# CPU.net
KiCad netlist of a schematic drawn in Altium Designer
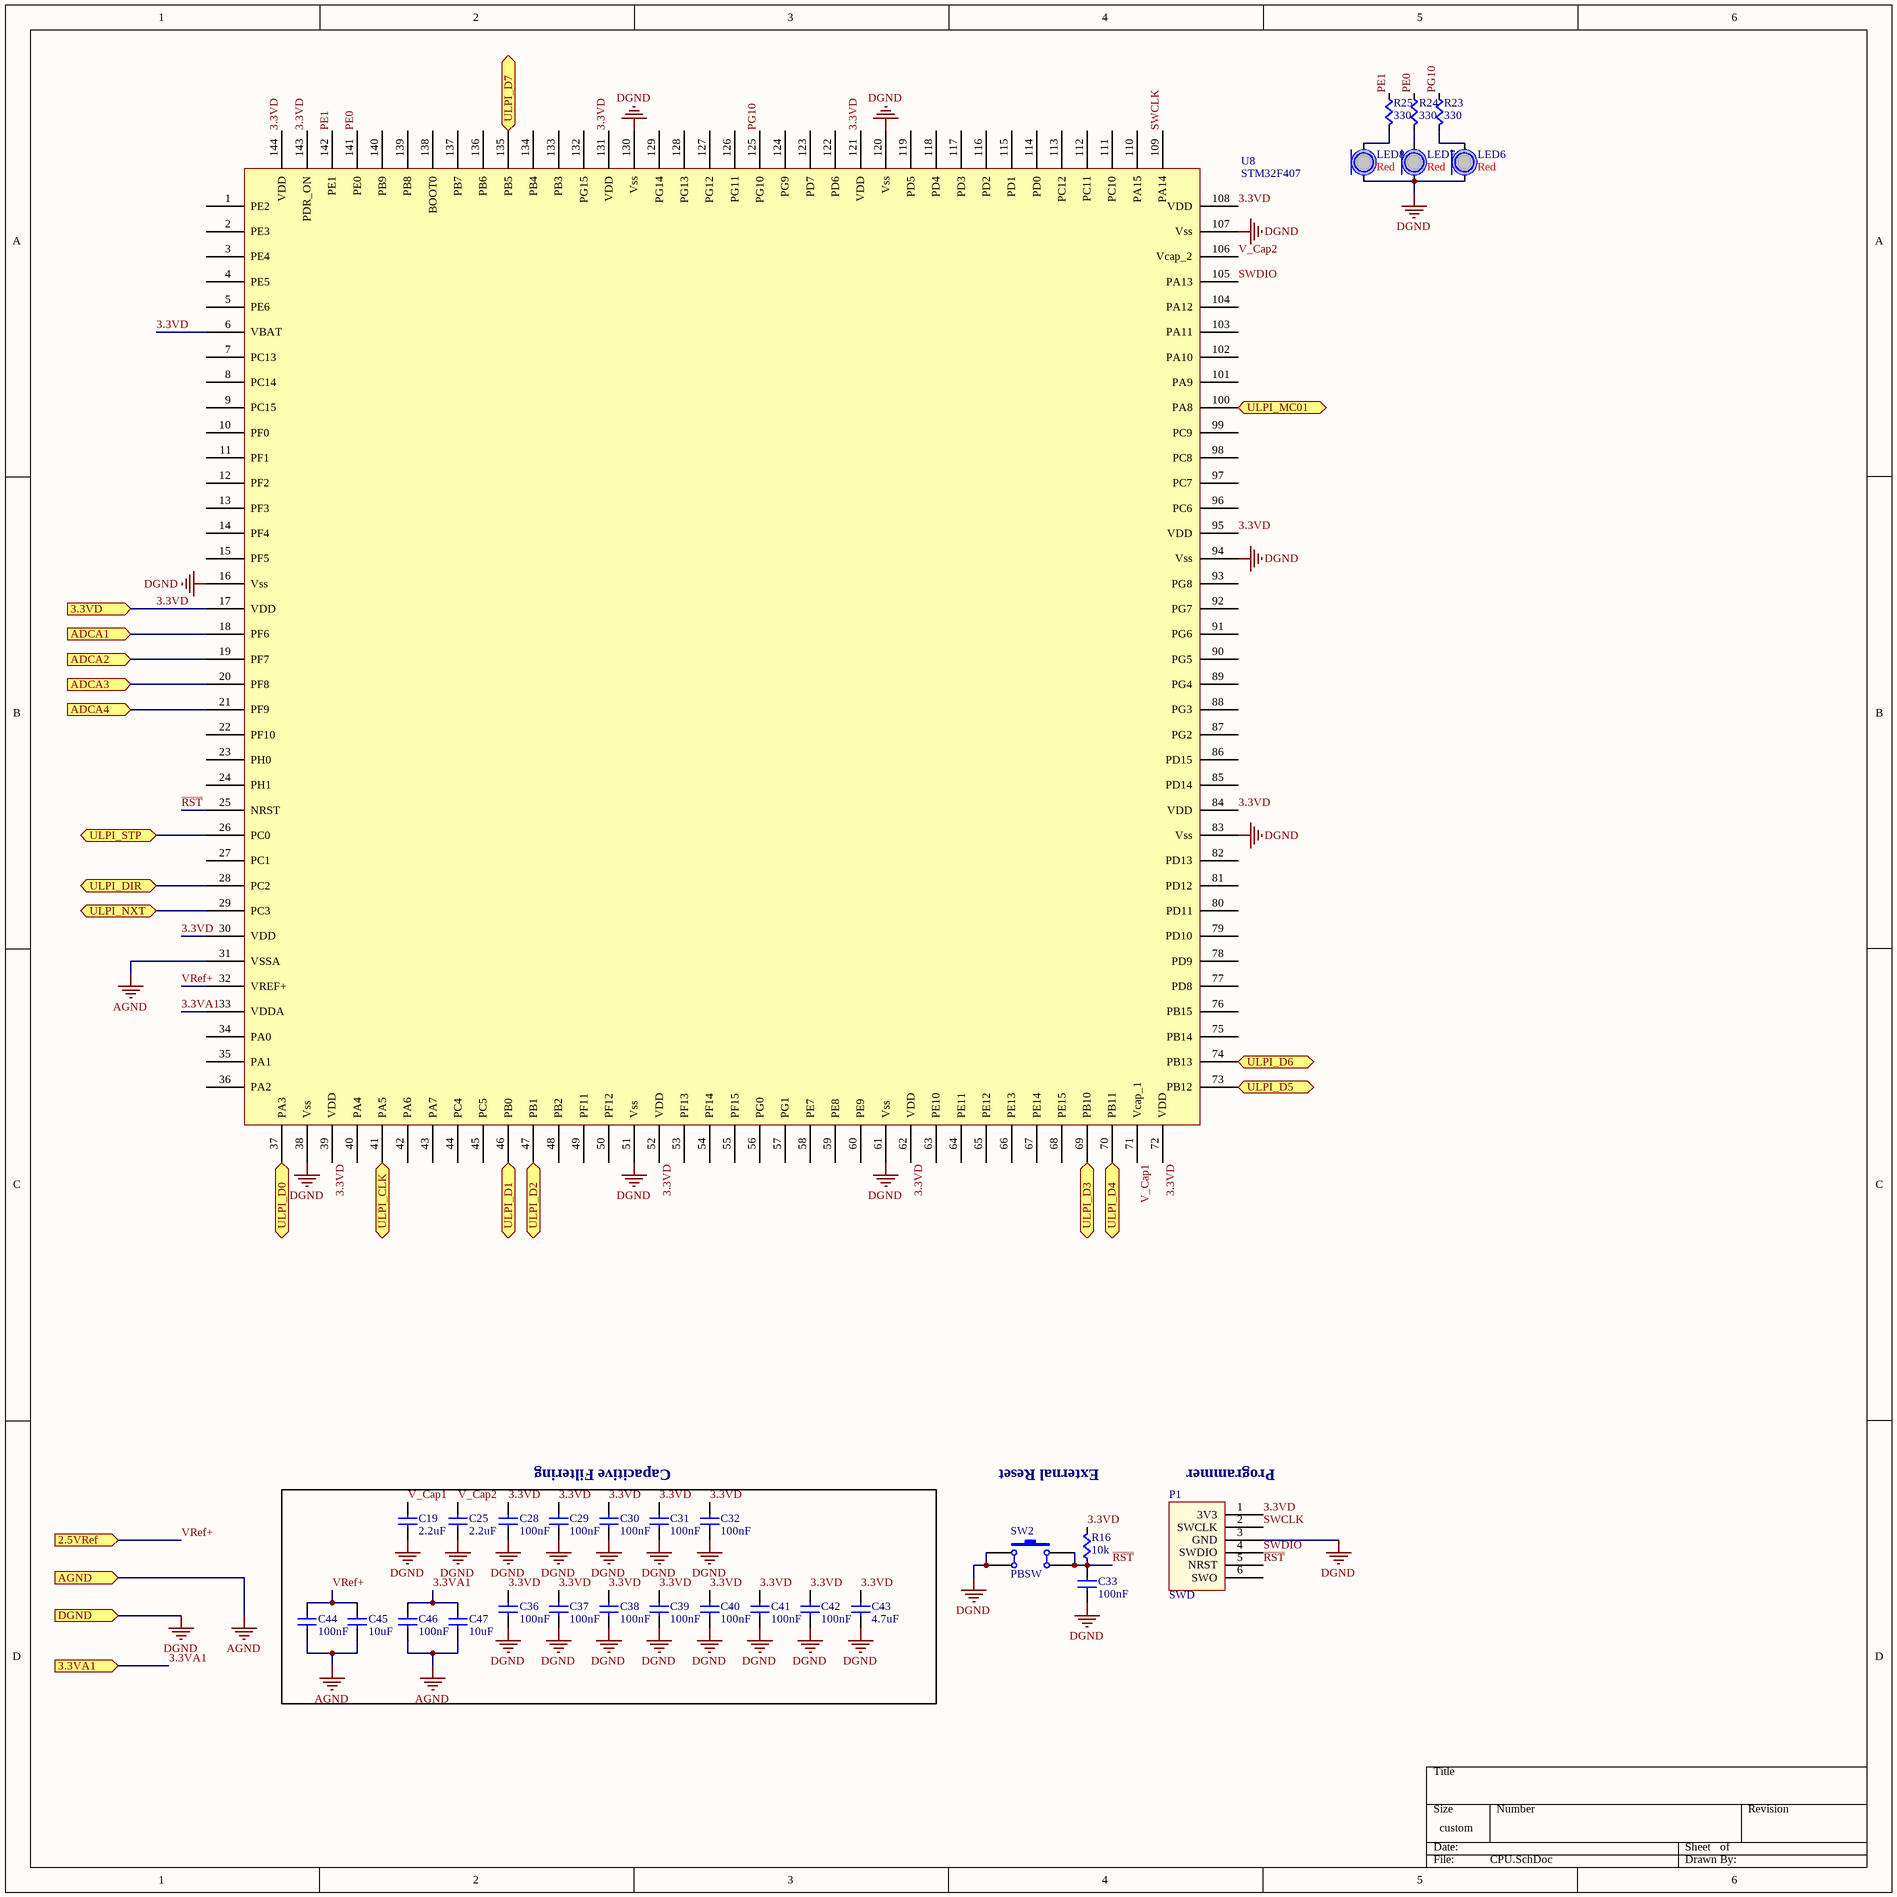
[diagram p0: CPU.SchDoc]

(export (version "E")
  (design (tool "Eeschema 10.0.6"))
  (components
    (comp (ref "C19")
      (value "2.2uF")
      (footprint "CAPC0603")
      (fields (field (name "Comment") "Cap"))
      (libsource (lib "SubjuGator8") (part "Cap"))
    )
    (comp (ref "C25")
      (value "2.2uF")
      (footprint "CAPC0603")
      (fields (field (name "Comment") "Cap"))
      (libsource (lib "SubjuGator8") (part "Cap"))
    )
    (comp (ref "C28")
      (value "100nF")
      (footprint "CAPC0603")
      (fields (field (name "Comment") "Cap"))
      (libsource (lib "SubjuGator8") (part "Cap"))
    )
    (comp (ref "C29")
      (value "100nF")
      (footprint "CAPC0603")
      (fields (field (name "Comment") "Cap"))
      (libsource (lib "SubjuGator8") (part "Cap"))
    )
    (comp (ref "C30")
      (value "100nF")
      (footprint "CAPC0603")
      (fields (field (name "Comment") "Cap"))
      (libsource (lib "SubjuGator8") (part "Cap"))
    )
    (comp (ref "C31")
      (value "100nF")
      (footprint "CAPC0603")
      (fields (field (name "Comment") "Cap"))
      (libsource (lib "SubjuGator8") (part "Cap"))
    )
    (comp (ref "C32")
      (value "100nF")
      (footprint "CAPC0603")
      (fields (field (name "Comment") "Cap"))
      (libsource (lib "SubjuGator8") (part "Cap"))
    )
    (comp (ref "C33")
      (value "100nF")
      (footprint "CAPC0603")
      (fields (field (name "Comment") "Cap"))
      (libsource (lib "SubjuGator8") (part "Cap"))
    )
    (comp (ref "C36")
      (value "100nF")
      (footprint "CAPC0603")
      (fields (field (name "Comment") "Cap"))
      (libsource (lib "SubjuGator8") (part "Cap"))
    )
    (comp (ref "C37")
      (value "100nF")
      (footprint "CAPC0603")
      (fields (field (name "Comment") "Cap"))
      (libsource (lib "SubjuGator8") (part "Cap"))
    )
    (comp (ref "C38")
      (value "100nF")
      (footprint "CAPC0603")
      (fields (field (name "Comment") "Cap"))
      (libsource (lib "SubjuGator8") (part "Cap"))
    )
    (comp (ref "C39")
      (value "100nF")
      (footprint "CAPC0603")
      (fields (field (name "Comment") "Cap"))
      (libsource (lib "SubjuGator8") (part "Cap"))
    )
    (comp (ref "C40")
      (value "100nF")
      (footprint "CAPC0603")
      (fields (field (name "Comment") "Cap"))
      (libsource (lib "SubjuGator8") (part "Cap"))
    )
    (comp (ref "C41")
      (value "100nF")
      (footprint "CAPC0603")
      (fields (field (name "Comment") "Cap"))
      (libsource (lib "SubjuGator8") (part "Cap"))
    )
    (comp (ref "C42")
      (value "100nF")
      (footprint "CAPC0603")
      (fields (field (name "Comment") "Cap"))
      (libsource (lib "SubjuGator8") (part "Cap"))
    )
    (comp (ref "C43")
      (value "4.7uF")
      (footprint "CAPC0603")
      (fields (field (name "Comment") "Cap"))
      (libsource (lib "SubjuGator8") (part "Cap"))
    )
    (comp (ref "C44")
      (value "100nF")
      (footprint "CAPC0603")
      (fields (field (name "Comment") "Cap"))
      (libsource (lib "SubjuGator8") (part "Cap"))
    )
    (comp (ref "C45")
      (value "10uF")
      (footprint "CAPC0603")
      (fields (field (name "Comment") "Cap"))
      (libsource (lib "SubjuGator8") (part "Cap"))
    )
    (comp (ref "C46")
      (value "100nF")
      (footprint "CAPC0603")
      (fields (field (name "Comment") "Cap"))
      (libsource (lib "SubjuGator8") (part "Cap"))
    )
    (comp (ref "C47")
      (value "10uF")
      (footprint "CAPC0603")
      (fields (field (name "Comment") "Cap"))
      (libsource (lib "SubjuGator8") (part "Cap"))
    )
    (comp (ref "LED6")
      (value "LED")
      (footprint "LED0603")
      (fields (field (name "COLOR") "Red"))
      (libsource (lib "Semiconductors") (part "LED"))
    )
    (comp (ref "LED7")
      (value "LED")
      (footprint "LED0603")
      (fields (field (name "COLOR") "Red"))
      (libsource (lib "Semiconductors") (part "LED"))
    )
    (comp (ref "LED8")
      (value "LED")
      (footprint "LED0603")
      (fields (field (name "COLOR") "Red"))
      (libsource (lib "Semiconductors") (part "LED"))
    )
    (comp (ref "P1")
      (value "SWD")
      (footprint "SWD_STM32")
      (description "SWD connector matching the pinout on STM Discovery Boards")
      (libsource (lib "SubjuGator8") (part "SWD_STM32"))
    )
    (comp (ref "R16")
      (value "10k")
      (footprint "RES0603")
      (fields (field (name "Comment") "Res"))
      (libsource (lib "Passives") (part "Res"))
    )
    (comp (ref "R23")
      (value "330")
      (footprint "RES0603")
      (fields (field (name "Comment") "Res"))
      (libsource (lib "Passives") (part "Res"))
    )
    (comp (ref "R24")
      (value "330")
      (footprint "RES0603")
      (fields (field (name "Comment") "Res"))
      (libsource (lib "Passives") (part "Res"))
    )
    (comp (ref "R25")
      (value "330")
      (footprint "RES0603")
      (fields (field (name "Comment") "Res"))
      (libsource (lib "Passives") (part "Res"))
    )
    (comp (ref "SW2")
      (value "PBSW")
      (footprint "Hydrophone:PBSW")
      (description "Push Button Switch")
      (fields
        (field (name "MANUFACTURER") "Panasonic Electronic Components")
        (field (name "MANUFACTURER PART NUMBER") "EVQ-9P105M")
        (field (name "PUBLISHER") "Altium Limited")
      )
      (libsource (lib "Hydrophone") (part "SW-PB"))
    )
    (comp (ref "U8")
      (value "STM32F407")
      (footprint "LQFP-144")
      (description "IC MCU 32BIT 1MB FLASH 144LQFP")
      (libsource (lib "SubjuGator8") (part "STM32F407ZGT6"))
    )
  )
  (nets
    (net (code "1") (name "/3.3VA1") (class "Default")
      (node (ref "C46") (pin "1") (pinfunction "A_1") (pintype "passive"))
      (node (ref "C47") (pin "1") (pinfunction "A_1") (pintype "passive"))
      (node (ref "U8") (pin "33") (pinfunction "VDDA_33") (pintype "passive"))
    )
    (net (code "2") (name "/3.3VD") (class "Default")
      (node (ref "C28") (pin "1") (pinfunction "A_1") (pintype "passive"))
      (node (ref "C29") (pin "1") (pinfunction "A_1") (pintype "passive"))
      (node (ref "C30") (pin "1") (pinfunction "A_1") (pintype "passive"))
      (node (ref "C31") (pin "1") (pinfunction "A_1") (pintype "passive"))
      (node (ref "C32") (pin "1") (pinfunction "A_1") (pintype "passive"))
      (node (ref "C36") (pin "1") (pinfunction "A_1") (pintype "passive"))
      (node (ref "C37") (pin "1") (pinfunction "A_1") (pintype "passive"))
      (node (ref "C38") (pin "1") (pinfunction "A_1") (pintype "passive"))
      (node (ref "C39") (pin "1") (pinfunction "A_1") (pintype "passive"))
      (node (ref "C40") (pin "1") (pinfunction "A_1") (pintype "passive"))
      (node (ref "C41") (pin "1") (pinfunction "A_1") (pintype "passive"))
      (node (ref "C42") (pin "1") (pinfunction "A_1") (pintype "passive"))
      (node (ref "C43") (pin "1") (pinfunction "A_1") (pintype "passive"))
      (node (ref "P1") (pin "1") (pinfunction "3V3_1") (pintype "passive"))
      (node (ref "R16") (pin "1") (pinfunction "A_1") (pintype "passive"))
      (node (ref "U8") (pin "108") (pinfunction "VDD_108") (pintype "passive"))
      (node (ref "U8") (pin "121") (pinfunction "VDD_121") (pintype "passive"))
      (node (ref "U8") (pin "131") (pinfunction "VDD_131") (pintype "passive"))
      (node (ref "U8") (pin "143") (pinfunction "PDR_ON_143") (pintype "passive"))
      (node (ref "U8") (pin "144") (pinfunction "VDD_144") (pintype "passive"))
      (node (ref "U8") (pin "17") (pinfunction "VDD_17") (pintype "passive"))
      (node (ref "U8") (pin "30") (pinfunction "VDD_30") (pintype "passive"))
      (node (ref "U8") (pin "39") (pinfunction "VDD_39") (pintype "passive"))
      (node (ref "U8") (pin "52") (pinfunction "VDD_52") (pintype "passive"))
      (node (ref "U8") (pin "6") (pinfunction "VBAT_6") (pintype "passive"))
      (node (ref "U8") (pin "62") (pinfunction "VDD_62") (pintype "passive"))
      (node (ref "U8") (pin "72") (pinfunction "VDD_72") (pintype "passive"))
      (node (ref "U8") (pin "84") (pinfunction "VDD_84") (pintype "passive"))
      (node (ref "U8") (pin "95") (pinfunction "VDD_95") (pintype "passive"))
    )
    (net (code "3") (name "/ADCA1") (class "Default")
      (node (ref "U8") (pin "18") (pinfunction "PF6_18") (pintype "passive"))
    )
    (net (code "4") (name "/ADCA2") (class "Default")
      (node (ref "U8") (pin "19") (pinfunction "PF7_19") (pintype "passive"))
    )
    (net (code "5") (name "/ADCA3") (class "Default")
      (node (ref "U8") (pin "20") (pinfunction "PF8_20") (pintype "passive"))
    )
    (net (code "6") (name "/ADCA4") (class "Default")
      (node (ref "U8") (pin "21") (pinfunction "PF9_21") (pintype "passive"))
    )
    (net (code "7") (name "/PE0") (class "Default")
      (node (ref "R24") (pin "2") (pinfunction "B_2") (pintype "passive"))
      (node (ref "U8") (pin "141") (pinfunction "PE0_141") (pintype "passive"))
    )
    (net (code "8") (name "/PE1") (class "Default")
      (node (ref "R25") (pin "2") (pinfunction "B_2") (pintype "passive"))
      (node (ref "U8") (pin "142") (pinfunction "PE1_142") (pintype "passive"))
    )
    (net (code "9") (name "/PG10") (class "Default")
      (node (ref "R23") (pin "2") (pinfunction "B_2") (pintype "passive"))
      (node (ref "U8") (pin "125") (pinfunction "PG10_125") (pintype "passive"))
    )
    (net (code "10") (name "/SWCLK") (class "Default")
      (node (ref "P1") (pin "2") (pinfunction "SWCLK_2") (pintype "passive"))
      (node (ref "U8") (pin "109") (pinfunction "PA14_109") (pintype "passive"))
    )
    (net (code "11") (name "/SWDIO") (class "Default")
      (node (ref "P1") (pin "4") (pinfunction "SWDIO_4") (pintype "passive"))
      (node (ref "U8") (pin "105") (pinfunction "PA13_105") (pintype "passive"))
    )
    (net (code "12") (name "/ULPI_CLK") (class "Default")
      (node (ref "U8") (pin "41") (pinfunction "PA5_41") (pintype "passive"))
    )
    (net (code "13") (name "/ULPI_D0") (class "Default")
      (node (ref "U8") (pin "37") (pinfunction "PA3_37") (pintype "passive"))
    )
    (net (code "14") (name "/ULPI_D1") (class "Default")
      (node (ref "U8") (pin "46") (pinfunction "PB0_46") (pintype "passive"))
    )
    (net (code "15") (name "/ULPI_D2") (class "Default")
      (node (ref "U8") (pin "47") (pinfunction "PB1_47") (pintype "passive"))
    )
    (net (code "16") (name "/ULPI_D3") (class "Default")
      (node (ref "U8") (pin "69") (pinfunction "PB10_69") (pintype "passive"))
    )
    (net (code "17") (name "/ULPI_D4") (class "Default")
      (node (ref "U8") (pin "70") (pinfunction "PB11_70") (pintype "passive"))
    )
    (net (code "18") (name "/ULPI_D5") (class "Default")
      (node (ref "U8") (pin "73") (pinfunction "PB12_73") (pintype "passive"))
    )
    (net (code "19") (name "/ULPI_D6") (class "Default")
      (node (ref "U8") (pin "74") (pinfunction "PB13_74") (pintype "passive"))
    )
    (net (code "20") (name "/ULPI_D7") (class "Default")
      (node (ref "U8") (pin "135") (pinfunction "PB5_135") (pintype "passive"))
    )
    (net (code "21") (name "/ULPI_DIR") (class "Default")
      (node (ref "U8") (pin "28") (pinfunction "PC2_28") (pintype "passive"))
    )
    (net (code "22") (name "/ULPI_MC01") (class "Default")
      (node (ref "U8") (pin "100") (pinfunction "PA8_100") (pintype "passive"))
    )
    (net (code "23") (name "/ULPI_NXT") (class "Default")
      (node (ref "U8") (pin "29") (pinfunction "PC3_29") (pintype "passive"))
    )
    (net (code "24") (name "/ULPI_STP") (class "Default")
      (node (ref "U8") (pin "26") (pinfunction "PC0_26") (pintype "passive"))
    )
    (net (code "25") (name "/VRef+") (class "Default")
      (node (ref "C44") (pin "1") (pinfunction "A_1") (pintype "passive"))
      (node (ref "C45") (pin "1") (pinfunction "A_1") (pintype "passive"))
      (node (ref "U8") (pin "32") (pinfunction "VREF+_32") (pintype "passive"))
    )
    (net (code "26") (name "/V_Cap1") (class "Default")
      (node (ref "C19") (pin "1") (pinfunction "A_1") (pintype "passive"))
      (node (ref "U8") (pin "71") (pinfunction "Vcap_1_71") (pintype "passive"))
    )
    (net (code "27") (name "/V_Cap2") (class "Default")
      (node (ref "C25") (pin "1") (pinfunction "A_1") (pintype "passive"))
      (node (ref "U8") (pin "106") (pinfunction "Vcap_2_106") (pintype "passive"))
    )
    (net (code "28") (name "/~{RST}") (class "Default")
      (node (ref "C33") (pin "1") (pinfunction "A_1") (pintype "passive"))
      (node (ref "P1") (pin "5") (pinfunction "NRST_5") (pintype "passive"))
      (node (ref "R16") (pin "2") (pinfunction "B_2") (pintype "passive"))
      (node (ref "SW2") (pin "3") (pinfunction "B_3") (pintype "passive"))
      (node (ref "SW2") (pin "4") (pinfunction "B'_4") (pintype "passive"))
      (node (ref "U8") (pin "25") (pinfunction "NRST_25") (pintype "passive"))
    )
    (net (code "29") (name "AGND") (class "Default")
      (node (ref "C44") (pin "2") (pinfunction "B_2") (pintype "passive"))
      (node (ref "C45") (pin "2") (pinfunction "B_2") (pintype "passive"))
      (node (ref "C46") (pin "2") (pinfunction "B_2") (pintype "passive"))
      (node (ref "C47") (pin "2") (pinfunction "B_2") (pintype "passive"))
      (node (ref "U8") (pin "31") (pinfunction "VSSA_31") (pintype "passive"))
    )
    (net (code "30") (name "DGND") (class "Default")
      (node (ref "C19") (pin "2") (pinfunction "B_2") (pintype "passive"))
      (node (ref "C25") (pin "2") (pinfunction "B_2") (pintype "passive"))
      (node (ref "C28") (pin "2") (pinfunction "B_2") (pintype "passive"))
      (node (ref "C29") (pin "2") (pinfunction "B_2") (pintype "passive"))
      (node (ref "C30") (pin "2") (pinfunction "B_2") (pintype "passive"))
      (node (ref "C31") (pin "2") (pinfunction "B_2") (pintype "passive"))
      (node (ref "C32") (pin "2") (pinfunction "B_2") (pintype "passive"))
      (node (ref "C33") (pin "2") (pinfunction "B_2") (pintype "passive"))
      (node (ref "C36") (pin "2") (pinfunction "B_2") (pintype "passive"))
      (node (ref "C37") (pin "2") (pinfunction "B_2") (pintype "passive"))
      (node (ref "C38") (pin "2") (pinfunction "B_2") (pintype "passive"))
      (node (ref "C39") (pin "2") (pinfunction "B_2") (pintype "passive"))
      (node (ref "C40") (pin "2") (pinfunction "B_2") (pintype "passive"))
      (node (ref "C41") (pin "2") (pinfunction "B_2") (pintype "passive"))
      (node (ref "C42") (pin "2") (pinfunction "B_2") (pintype "passive"))
      (node (ref "C43") (pin "2") (pinfunction "B_2") (pintype "passive"))
      (node (ref "LED6") (pin "C") (pinfunction "C_C") (pintype "passive"))
      (node (ref "LED7") (pin "C") (pinfunction "C_C") (pintype "passive"))
      (node (ref "LED8") (pin "C") (pinfunction "C_C") (pintype "passive"))
      (node (ref "P1") (pin "3") (pinfunction "GND_3") (pintype "passive"))
      (node (ref "SW2") (pin "1") (pinfunction "A_1") (pintype "passive"))
      (node (ref "SW2") (pin "2") (pinfunction "A'_2") (pintype "passive"))
      (node (ref "U8") (pin "107") (pinfunction "Vss_107") (pintype "passive"))
      (node (ref "U8") (pin "120") (pinfunction "Vss_120") (pintype "passive"))
      (node (ref "U8") (pin "130") (pinfunction "Vss_130") (pintype "passive"))
      (node (ref "U8") (pin "16") (pinfunction "Vss_16") (pintype "passive"))
      (node (ref "U8") (pin "38") (pinfunction "Vss_38") (pintype "passive"))
      (node (ref "U8") (pin "51") (pinfunction "Vss_51") (pintype "passive"))
      (node (ref "U8") (pin "61") (pinfunction "Vss_61") (pintype "passive"))
      (node (ref "U8") (pin "83") (pinfunction "Vss_83") (pintype "passive"))
      (node (ref "U8") (pin "94") (pinfunction "Vss_94") (pintype "passive"))
    )
    (net (code "31") (name "Net-(R23-A)") (class "Default")
      (node (ref "LED6") (pin "A") (pinfunction "A_A") (pintype "passive"))
      (node (ref "R23") (pin "1") (pinfunction "A_1") (pintype "passive"))
    )
    (net (code "32") (name "Net-(R24-A)") (class "Default")
      (node (ref "LED7") (pin "A") (pinfunction "A_A") (pintype "passive"))
      (node (ref "R24") (pin "1") (pinfunction "A_1") (pintype "passive"))
    )
    (net (code "33") (name "Net-(R25-A)") (class "Default")
      (node (ref "LED8") (pin "A") (pinfunction "A_A") (pintype "passive"))
      (node (ref "R25") (pin "1") (pinfunction "A_1") (pintype "passive"))
    )
    (net (code "34") (name "unconnected-(P1-SWO-Pad6)") (class "Default")
      (node (ref "P1") (pin "6") (pinfunction "SWO_6") (pintype "passive"))
    )
    (net (code "35") (name "unconnected-(U8-BOOT0-Pad138)") (class "Default")
      (node (ref "U8") (pin "138") (pinfunction "BOOT0_138") (pintype "passive"))
    )
    (net (code "36") (name "unconnected-(U8-PA0-Pad34)") (class "Default")
      (node (ref "U8") (pin "34") (pinfunction "PA0_34") (pintype "passive"))
    )
    (net (code "37") (name "unconnected-(U8-PA1-Pad35)") (class "Default")
      (node (ref "U8") (pin "35") (pinfunction "PA1_35") (pintype "passive"))
    )
    (net (code "38") (name "unconnected-(U8-PA2-Pad36)") (class "Default")
      (node (ref "U8") (pin "36") (pinfunction "PA2_36") (pintype "passive"))
    )
    (net (code "39") (name "unconnected-(U8-PA4-Pad40)") (class "Default")
      (node (ref "U8") (pin "40") (pinfunction "PA4_40") (pintype "passive"))
    )
    (net (code "40") (name "unconnected-(U8-PA6-Pad42)") (class "Default")
      (node (ref "U8") (pin "42") (pinfunction "PA6_42") (pintype "passive"))
    )
    (net (code "41") (name "unconnected-(U8-PA7-Pad43)") (class "Default")
      (node (ref "U8") (pin "43") (pinfunction "PA7_43") (pintype "passive"))
    )
    (net (code "42") (name "unconnected-(U8-PA9-Pad101)") (class "Default")
      (node (ref "U8") (pin "101") (pinfunction "PA9_101") (pintype "passive"))
    )
    (net (code "43") (name "unconnected-(U8-PA10-Pad102)") (class "Default")
      (node (ref "U8") (pin "102") (pinfunction "PA10_102") (pintype "passive"))
    )
    (net (code "44") (name "unconnected-(U8-PA11-Pad103)") (class "Default")
      (node (ref "U8") (pin "103") (pinfunction "PA11_103") (pintype "passive"))
    )
    (net (code "45") (name "unconnected-(U8-PA12-Pad104)") (class "Default")
      (node (ref "U8") (pin "104") (pinfunction "PA12_104") (pintype "passive"))
    )
    (net (code "46") (name "unconnected-(U8-PA15-Pad110)") (class "Default")
      (node (ref "U8") (pin "110") (pinfunction "PA15_110") (pintype "passive"))
    )
    (net (code "47") (name "unconnected-(U8-PB2-Pad48)") (class "Default")
      (node (ref "U8") (pin "48") (pinfunction "PB2_48") (pintype "passive"))
    )
    (net (code "48") (name "unconnected-(U8-PB3-Pad133)") (class "Default")
      (node (ref "U8") (pin "133") (pinfunction "PB3_133") (pintype "passive"))
    )
    (net (code "49") (name "unconnected-(U8-PB4-Pad134)") (class "Default")
      (node (ref "U8") (pin "134") (pinfunction "PB4_134") (pintype "passive"))
    )
    (net (code "50") (name "unconnected-(U8-PB6-Pad136)") (class "Default")
      (node (ref "U8") (pin "136") (pinfunction "PB6_136") (pintype "passive"))
    )
    (net (code "51") (name "unconnected-(U8-PB7-Pad137)") (class "Default")
      (node (ref "U8") (pin "137") (pinfunction "PB7_137") (pintype "passive"))
    )
    (net (code "52") (name "unconnected-(U8-PB8-Pad139)") (class "Default")
      (node (ref "U8") (pin "139") (pinfunction "PB8_139") (pintype "passive"))
    )
    (net (code "53") (name "unconnected-(U8-PB9-Pad140)") (class "Default")
      (node (ref "U8") (pin "140") (pinfunction "PB9_140") (pintype "passive"))
    )
    (net (code "54") (name "unconnected-(U8-PB14-Pad75)") (class "Default")
      (node (ref "U8") (pin "75") (pinfunction "PB14_75") (pintype "passive"))
    )
    (net (code "55") (name "unconnected-(U8-PB15-Pad76)") (class "Default")
      (node (ref "U8") (pin "76") (pinfunction "PB15_76") (pintype "passive"))
    )
    (net (code "56") (name "unconnected-(U8-PC1-Pad27)") (class "Default")
      (node (ref "U8") (pin "27") (pinfunction "PC1_27") (pintype "passive"))
    )
    (net (code "57") (name "unconnected-(U8-PC4-Pad44)") (class "Default")
      (node (ref "U8") (pin "44") (pinfunction "PC4_44") (pintype "passive"))
    )
    (net (code "58") (name "unconnected-(U8-PC5-Pad45)") (class "Default")
      (node (ref "U8") (pin "45") (pinfunction "PC5_45") (pintype "passive"))
    )
    (net (code "59") (name "unconnected-(U8-PC6-Pad96)") (class "Default")
      (node (ref "U8") (pin "96") (pinfunction "PC6_96") (pintype "passive"))
    )
    (net (code "60") (name "unconnected-(U8-PC7-Pad97)") (class "Default")
      (node (ref "U8") (pin "97") (pinfunction "PC7_97") (pintype "passive"))
    )
    (net (code "61") (name "unconnected-(U8-PC8-Pad98)") (class "Default")
      (node (ref "U8") (pin "98") (pinfunction "PC8_98") (pintype "passive"))
    )
    (net (code "62") (name "unconnected-(U8-PC9-Pad99)") (class "Default")
      (node (ref "U8") (pin "99") (pinfunction "PC9_99") (pintype "passive"))
    )
    (net (code "63") (name "unconnected-(U8-PC10-Pad111)") (class "Default")
      (node (ref "U8") (pin "111") (pinfunction "PC10_111") (pintype "passive"))
    )
    (net (code "64") (name "unconnected-(U8-PC11-Pad112)") (class "Default")
      (node (ref "U8") (pin "112") (pinfunction "PC11_112") (pintype "passive"))
    )
    (net (code "65") (name "unconnected-(U8-PC12-Pad113)") (class "Default")
      (node (ref "U8") (pin "113") (pinfunction "PC12_113") (pintype "passive"))
    )
    (net (code "66") (name "unconnected-(U8-PC13-Pad7)") (class "Default")
      (node (ref "U8") (pin "7") (pinfunction "PC13_7") (pintype "passive"))
    )
    (net (code "67") (name "unconnected-(U8-PC14-Pad8)") (class "Default")
      (node (ref "U8") (pin "8") (pinfunction "PC14_8") (pintype "passive"))
    )
    (net (code "68") (name "unconnected-(U8-PC15-Pad9)") (class "Default")
      (node (ref "U8") (pin "9") (pinfunction "PC15_9") (pintype "passive"))
    )
    (net (code "69") (name "unconnected-(U8-PD0-Pad114)") (class "Default")
      (node (ref "U8") (pin "114") (pinfunction "PD0_114") (pintype "passive"))
    )
    (net (code "70") (name "unconnected-(U8-PD1-Pad115)") (class "Default")
      (node (ref "U8") (pin "115") (pinfunction "PD1_115") (pintype "passive"))
    )
    (net (code "71") (name "unconnected-(U8-PD2-Pad116)") (class "Default")
      (node (ref "U8") (pin "116") (pinfunction "PD2_116") (pintype "passive"))
    )
    (net (code "72") (name "unconnected-(U8-PD3-Pad117)") (class "Default")
      (node (ref "U8") (pin "117") (pinfunction "PD3_117") (pintype "passive"))
    )
    (net (code "73") (name "unconnected-(U8-PD4-Pad118)") (class "Default")
      (node (ref "U8") (pin "118") (pinfunction "PD4_118") (pintype "passive"))
    )
    (net (code "74") (name "unconnected-(U8-PD5-Pad119)") (class "Default")
      (node (ref "U8") (pin "119") (pinfunction "PD5_119") (pintype "passive"))
    )
    (net (code "75") (name "unconnected-(U8-PD6-Pad122)") (class "Default")
      (node (ref "U8") (pin "122") (pinfunction "PD6_122") (pintype "passive"))
    )
    (net (code "76") (name "unconnected-(U8-PD7-Pad123)") (class "Default")
      (node (ref "U8") (pin "123") (pinfunction "PD7_123") (pintype "passive"))
    )
    (net (code "77") (name "unconnected-(U8-PD8-Pad77)") (class "Default")
      (node (ref "U8") (pin "77") (pinfunction "PD8_77") (pintype "passive"))
    )
    (net (code "78") (name "unconnected-(U8-PD9-Pad78)") (class "Default")
      (node (ref "U8") (pin "78") (pinfunction "PD9_78") (pintype "passive"))
    )
    (net (code "79") (name "unconnected-(U8-PD10-Pad79)") (class "Default")
      (node (ref "U8") (pin "79") (pinfunction "PD10_79") (pintype "passive"))
    )
    (net (code "80") (name "unconnected-(U8-PD11-Pad80)") (class "Default")
      (node (ref "U8") (pin "80") (pinfunction "PD11_80") (pintype "passive"))
    )
    (net (code "81") (name "unconnected-(U8-PD12-Pad81)") (class "Default")
      (node (ref "U8") (pin "81") (pinfunction "PD12_81") (pintype "passive"))
    )
    (net (code "82") (name "unconnected-(U8-PD13-Pad82)") (class "Default")
      (node (ref "U8") (pin "82") (pinfunction "PD13_82") (pintype "passive"))
    )
    (net (code "83") (name "unconnected-(U8-PD14-Pad85)") (class "Default")
      (node (ref "U8") (pin "85") (pinfunction "PD14_85") (pintype "passive"))
    )
    (net (code "84") (name "unconnected-(U8-PD15-Pad86)") (class "Default")
      (node (ref "U8") (pin "86") (pinfunction "PD15_86") (pintype "passive"))
    )
    (net (code "85") (name "unconnected-(U8-PE2-Pad1)") (class "Default")
      (node (ref "U8") (pin "1") (pinfunction "PE2_1") (pintype "passive"))
    )
    (net (code "86") (name "unconnected-(U8-PE3-Pad2)") (class "Default")
      (node (ref "U8") (pin "2") (pinfunction "PE3_2") (pintype "passive"))
    )
    (net (code "87") (name "unconnected-(U8-PE4-Pad3)") (class "Default")
      (node (ref "U8") (pin "3") (pinfunction "PE4_3") (pintype "passive"))
    )
    (net (code "88") (name "unconnected-(U8-PE5-Pad4)") (class "Default")
      (node (ref "U8") (pin "4") (pinfunction "PE5_4") (pintype "passive"))
    )
    (net (code "89") (name "unconnected-(U8-PE6-Pad5)") (class "Default")
      (node (ref "U8") (pin "5") (pinfunction "PE6_5") (pintype "passive"))
    )
    (net (code "90") (name "unconnected-(U8-PE7-Pad58)") (class "Default")
      (node (ref "U8") (pin "58") (pinfunction "PE7_58") (pintype "passive"))
    )
    (net (code "91") (name "unconnected-(U8-PE8-Pad59)") (class "Default")
      (node (ref "U8") (pin "59") (pinfunction "PE8_59") (pintype "passive"))
    )
    (net (code "92") (name "unconnected-(U8-PE9-Pad60)") (class "Default")
      (node (ref "U8") (pin "60") (pinfunction "PE9_60") (pintype "passive"))
    )
    (net (code "93") (name "unconnected-(U8-PE10-Pad63)") (class "Default")
      (node (ref "U8") (pin "63") (pinfunction "PE10_63") (pintype "passive"))
    )
    (net (code "94") (name "unconnected-(U8-PE11-Pad64)") (class "Default")
      (node (ref "U8") (pin "64") (pinfunction "PE11_64") (pintype "passive"))
    )
    (net (code "95") (name "unconnected-(U8-PE12-Pad65)") (class "Default")
      (node (ref "U8") (pin "65") (pinfunction "PE12_65") (pintype "passive"))
    )
    (net (code "96") (name "unconnected-(U8-PE13-Pad66)") (class "Default")
      (node (ref "U8") (pin "66") (pinfunction "PE13_66") (pintype "passive"))
    )
    (net (code "97") (name "unconnected-(U8-PE14-Pad67)") (class "Default")
      (node (ref "U8") (pin "67") (pinfunction "PE14_67") (pintype "passive"))
    )
    (net (code "98") (name "unconnected-(U8-PE15-Pad68)") (class "Default")
      (node (ref "U8") (pin "68") (pinfunction "PE15_68") (pintype "passive"))
    )
    (net (code "99") (name "unconnected-(U8-PF0-Pad10)") (class "Default")
      (node (ref "U8") (pin "10") (pinfunction "PF0_10") (pintype "passive"))
    )
    (net (code "100") (name "unconnected-(U8-PF1-Pad11)") (class "Default")
      (node (ref "U8") (pin "11") (pinfunction "PF1_11") (pintype "passive"))
    )
    (net (code "101") (name "unconnected-(U8-PF2-Pad12)") (class "Default")
      (node (ref "U8") (pin "12") (pinfunction "PF2_12") (pintype "passive"))
    )
    (net (code "102") (name "unconnected-(U8-PF3-Pad13)") (class "Default")
      (node (ref "U8") (pin "13") (pinfunction "PF3_13") (pintype "passive"))
    )
    (net (code "103") (name "unconnected-(U8-PF4-Pad14)") (class "Default")
      (node (ref "U8") (pin "14") (pinfunction "PF4_14") (pintype "passive"))
    )
    (net (code "104") (name "unconnected-(U8-PF5-Pad15)") (class "Default")
      (node (ref "U8") (pin "15") (pinfunction "PF5_15") (pintype "passive"))
    )
    (net (code "105") (name "unconnected-(U8-PF10-Pad22)") (class "Default")
      (node (ref "U8") (pin "22") (pinfunction "PF10_22") (pintype "passive"))
    )
    (net (code "106") (name "unconnected-(U8-PF11-Pad49)") (class "Default")
      (node (ref "U8") (pin "49") (pinfunction "PF11_49") (pintype "passive"))
    )
    (net (code "107") (name "unconnected-(U8-PF12-Pad50)") (class "Default")
      (node (ref "U8") (pin "50") (pinfunction "PF12_50") (pintype "passive"))
    )
    (net (code "108") (name "unconnected-(U8-PF13-Pad53)") (class "Default")
      (node (ref "U8") (pin "53") (pinfunction "PF13_53") (pintype "passive"))
    )
    (net (code "109") (name "unconnected-(U8-PF14-Pad54)") (class "Default")
      (node (ref "U8") (pin "54") (pinfunction "PF14_54") (pintype "passive"))
    )
    (net (code "110") (name "unconnected-(U8-PF15-Pad55)") (class "Default")
      (node (ref "U8") (pin "55") (pinfunction "PF15_55") (pintype "passive"))
    )
    (net (code "111") (name "unconnected-(U8-PG0-Pad56)") (class "Default")
      (node (ref "U8") (pin "56") (pinfunction "PG0_56") (pintype "passive"))
    )
    (net (code "112") (name "unconnected-(U8-PG1-Pad57)") (class "Default")
      (node (ref "U8") (pin "57") (pinfunction "PG1_57") (pintype "passive"))
    )
    (net (code "113") (name "unconnected-(U8-PG2-Pad87)") (class "Default")
      (node (ref "U8") (pin "87") (pinfunction "PG2_87") (pintype "passive"))
    )
    (net (code "114") (name "unconnected-(U8-PG3-Pad88)") (class "Default")
      (node (ref "U8") (pin "88") (pinfunction "PG3_88") (pintype "passive"))
    )
    (net (code "115") (name "unconnected-(U8-PG4-Pad89)") (class "Default")
      (node (ref "U8") (pin "89") (pinfunction "PG4_89") (pintype "passive"))
    )
    (net (code "116") (name "unconnected-(U8-PG5-Pad90)") (class "Default")
      (node (ref "U8") (pin "90") (pinfunction "PG5_90") (pintype "passive"))
    )
    (net (code "117") (name "unconnected-(U8-PG6-Pad91)") (class "Default")
      (node (ref "U8") (pin "91") (pinfunction "PG6_91") (pintype "passive"))
    )
    (net (code "118") (name "unconnected-(U8-PG7-Pad92)") (class "Default")
      (node (ref "U8") (pin "92") (pinfunction "PG7_92") (pintype "passive"))
    )
    (net (code "119") (name "unconnected-(U8-PG8-Pad93)") (class "Default")
      (node (ref "U8") (pin "93") (pinfunction "PG8_93") (pintype "passive"))
    )
    (net (code "120") (name "unconnected-(U8-PG9-Pad124)") (class "Default")
      (node (ref "U8") (pin "124") (pinfunction "PG9_124") (pintype "passive"))
    )
    (net (code "121") (name "unconnected-(U8-PG11-Pad126)") (class "Default")
      (node (ref "U8") (pin "126") (pinfunction "PG11_126") (pintype "passive"))
    )
    (net (code "122") (name "unconnected-(U8-PG12-Pad127)") (class "Default")
      (node (ref "U8") (pin "127") (pinfunction "PG12_127") (pintype "passive"))
    )
    (net (code "123") (name "unconnected-(U8-PG13-Pad128)") (class "Default")
      (node (ref "U8") (pin "128") (pinfunction "PG13_128") (pintype "passive"))
    )
    (net (code "124") (name "unconnected-(U8-PG14-Pad129)") (class "Default")
      (node (ref "U8") (pin "129") (pinfunction "PG14_129") (pintype "passive"))
    )
    (net (code "125") (name "unconnected-(U8-PG15-Pad132)") (class "Default")
      (node (ref "U8") (pin "132") (pinfunction "PG15_132") (pintype "passive"))
    )
    (net (code "126") (name "unconnected-(U8-PH0-Pad23)") (class "Default")
      (node (ref "U8") (pin "23") (pinfunction "PH0_23") (pintype "passive"))
    )
    (net (code "127") (name "unconnected-(U8-PH1-Pad24)") (class "Default")
      (node (ref "U8") (pin "24") (pinfunction "PH1_24") (pintype "passive"))
    )
  )
)
